# -NFC.net
KiCad netlist of a schematic drawn in EasyEDA Pro
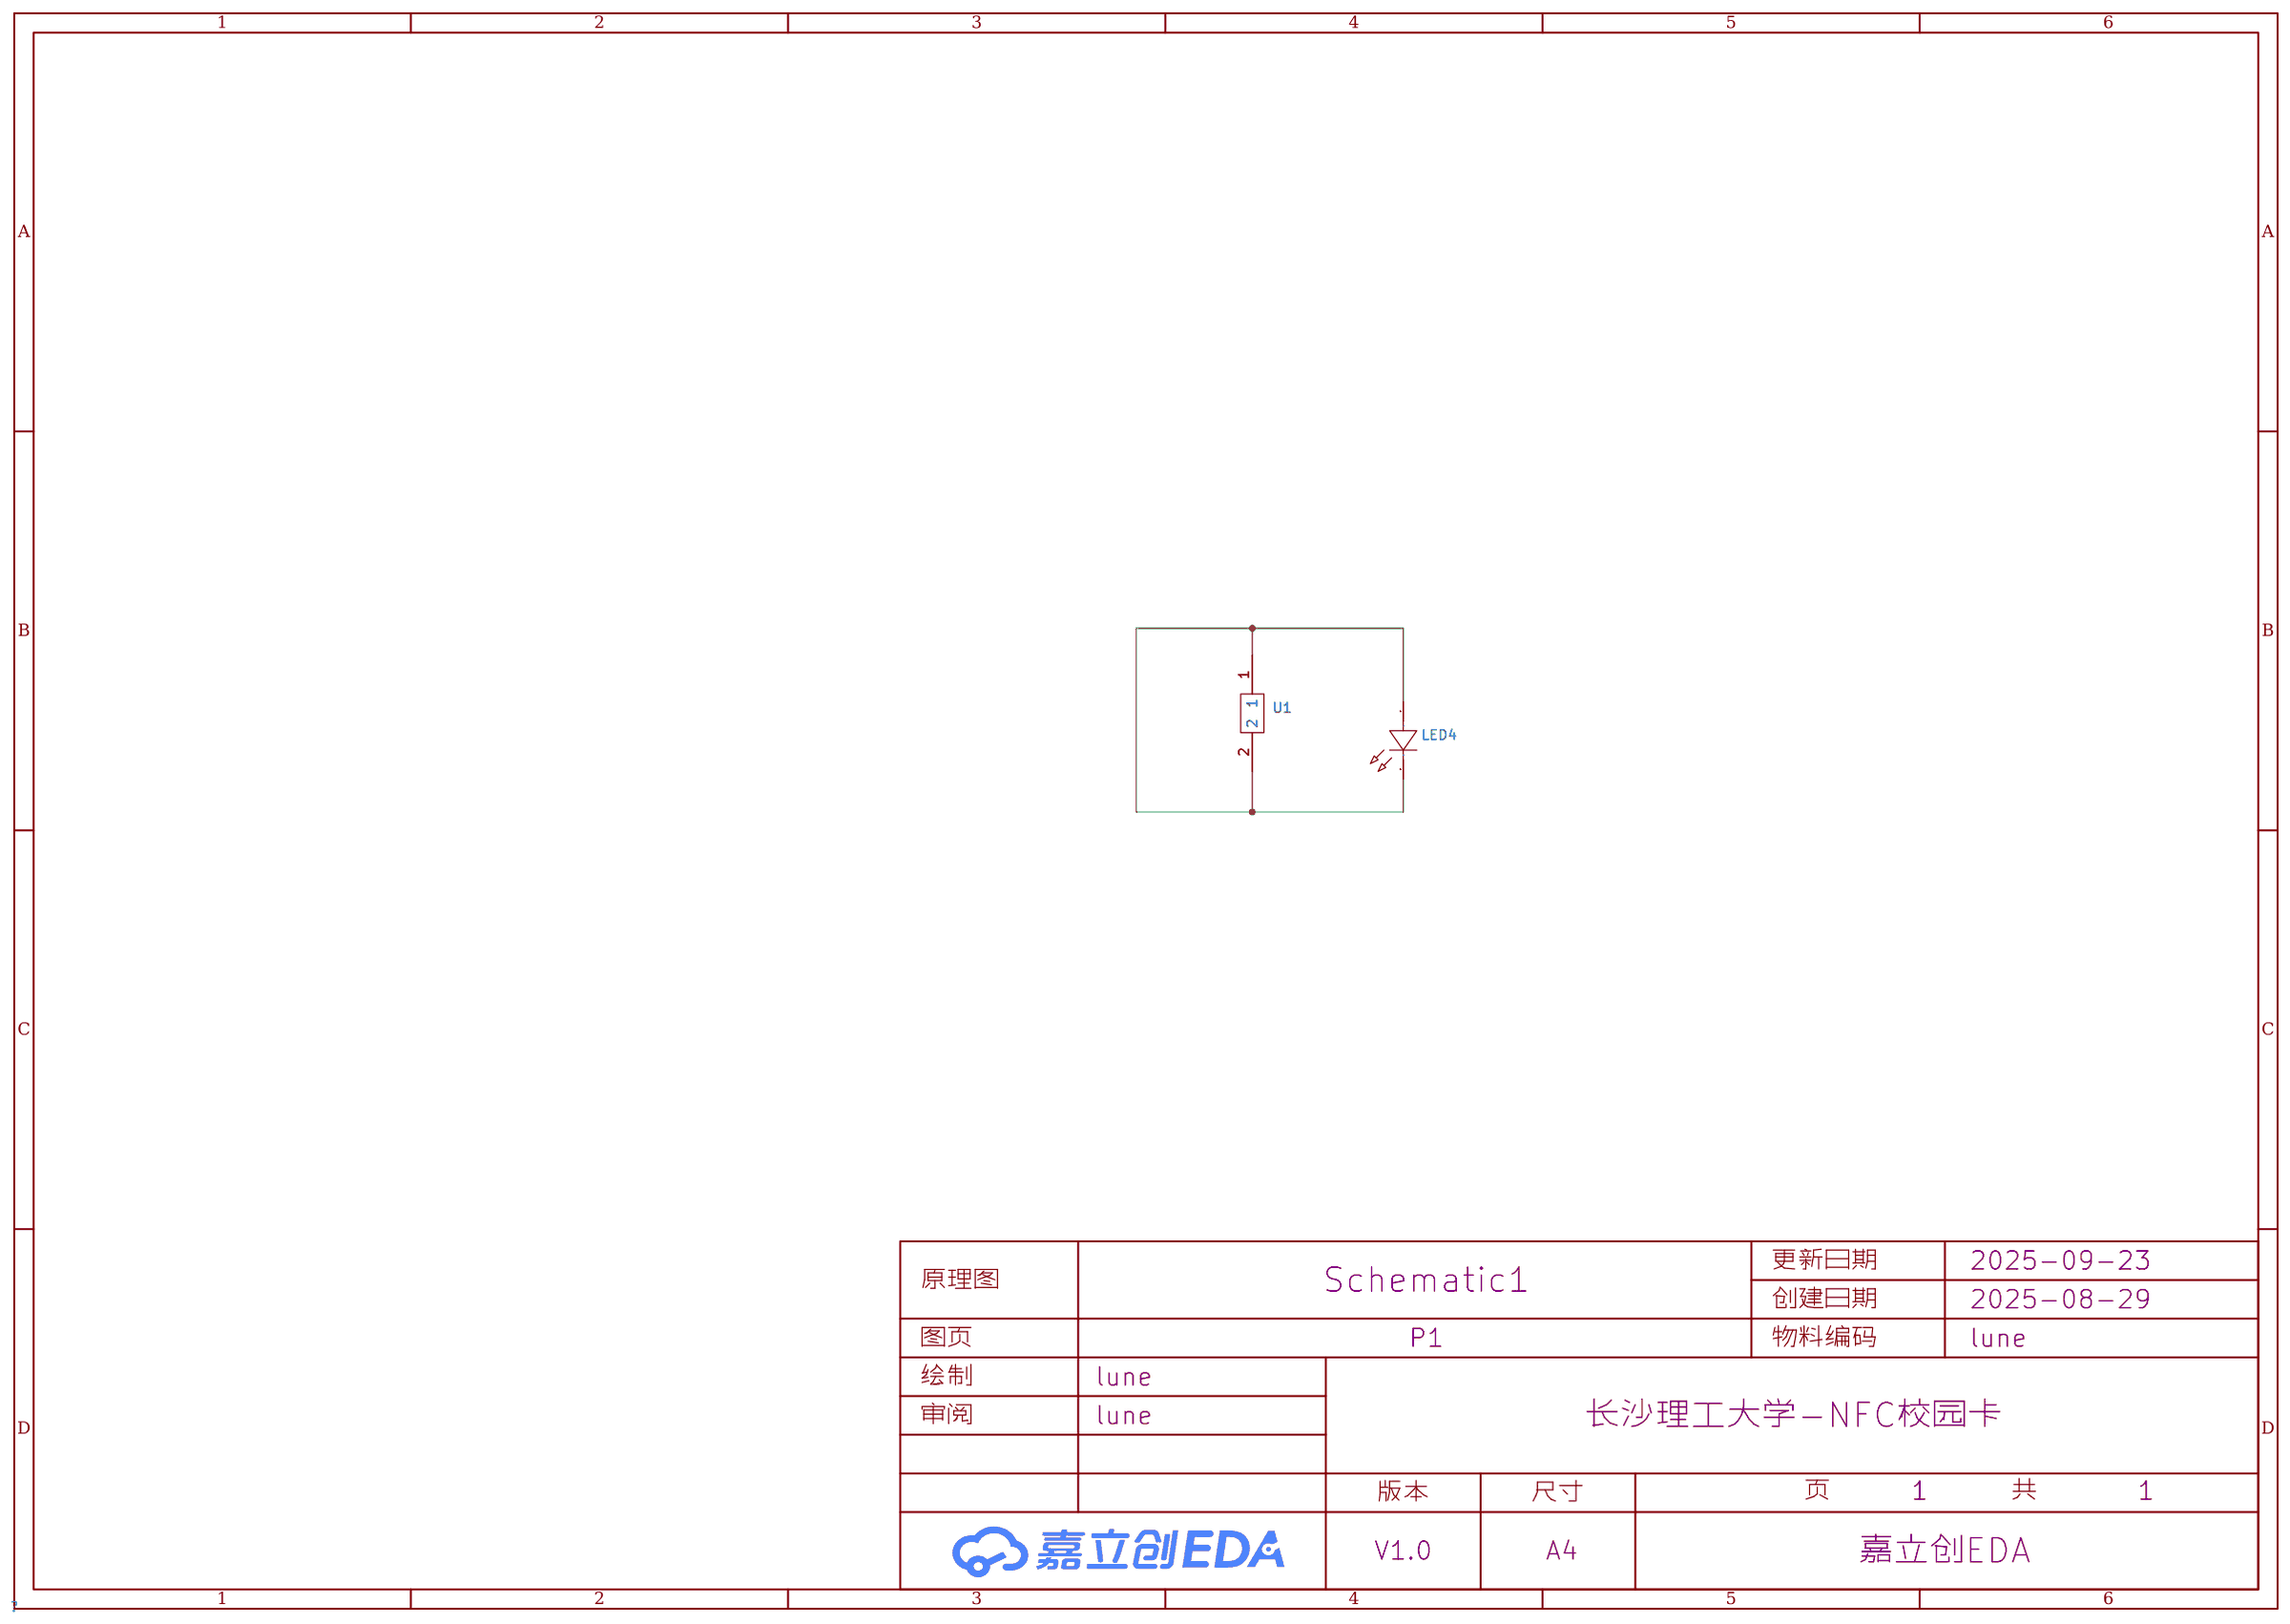
[diagram p0: schematic sheet]

(export (version "E")
  (design (tool "Eeschema 10.0.6"))
  (components
    (comp (ref "LED4")
      (value "XL-3216SURC")
      (footprint "easyedapro:LED1206-R-RD_RED")
      (description "发光颜色:红色;功率:55mW;正向电流:25mA;主波长:617nm~621nm;透镜颜色:无色透明透镜;色温:-;发光角度:120°;载带方式:正贴;工作温度:-30°C~+85°C;")
      (fields (field (name "Manufacturer") "XINGLIGHT(成兴光)"))
      (libsource (lib "easyedapro") (part "XL-3216SURC"))
    )
    (comp (ref "U1")
      (value "CUID")
      (footprint "easyedapro:CUID芯片5×8mm")
      (libsource (lib "easyedapro") (part "CUID芯片"))
    )
  )
  (nets
    (net (code "1") (name "Net-(LED4-A)") (class "Default")
      (node (ref "LED4") (pin "1") (pinfunction "K_1") (pintype "unspecified"))
      (node (ref "LED4") (pin "2") (pinfunction "A_2") (pintype "unspecified"))
      (node (ref "U1") (pin "1") (pinfunction "1_1") (pintype "input"))
      (node (ref "U1") (pin "2") (pinfunction "2_2") (pintype "input"))
    )
  )
)
